# jacare.net
KiCad netlist of a schematic drawn in EAGLE
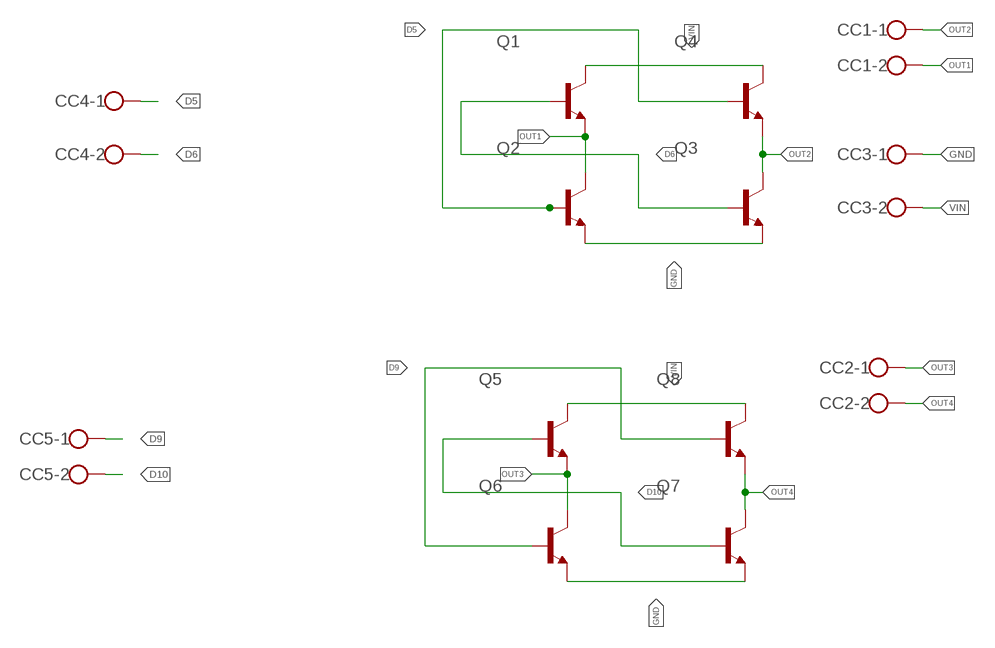
[diagram p0: schematic, sheet 1]

(export (version "E")
  (design (tool "Eeschema 10.0.6"))
  (components
    (comp (ref "CC1")
      (value "W237-102")
      (footprint "eagle-import:W237-102")
      (fields (field (name "MPN") "237-102"))
      (libsource (lib "eagle-import") (part "W237-102"))
    )
    (comp (ref "CC2")
      (value "W237-102")
      (footprint "eagle-import:W237-102")
      (fields (field (name "MPN") "237-102"))
      (libsource (lib "eagle-import") (part "W237-102"))
    )
    (comp (ref "CC3")
      (value "W237-102")
      (footprint "eagle-import:W237-102")
      (fields (field (name "MPN") "237-102"))
      (libsource (lib "eagle-import") (part "W237-102"))
    )
    (comp (ref "CC4")
      (value "W237-102")
      (footprint "eagle-import:W237-102")
      (fields (field (name "MPN") "237-102"))
      (libsource (lib "eagle-import") (part "W237-102"))
    )
    (comp (ref "CC5")
      (value "W237-102")
      (footprint "eagle-import:W237-102")
      (fields (field (name "MPN") "237-102"))
      (libsource (lib "eagle-import") (part "W237-102"))
    )
    (comp (ref "Q1")
      (value "-NPN-TO220V")
      (footprint "eagle-import:TO220V")
      (libsource (lib "eagle-import") (part "-NPN-TO220V"))
    )
    (comp (ref "Q2")
      (value "-NPN-TO220V")
      (footprint "eagle-import:TO220V")
      (libsource (lib "eagle-import") (part "-NPN-TO220V"))
    )
    (comp (ref "Q3")
      (value "-NPN-TO220V")
      (footprint "eagle-import:TO220V")
      (libsource (lib "eagle-import") (part "-NPN-TO220V"))
    )
    (comp (ref "Q4")
      (value "-NPN-TO220V")
      (footprint "eagle-import:TO220V")
      (libsource (lib "eagle-import") (part "-NPN-TO220V"))
    )
    (comp (ref "Q5")
      (value "-NPN-TO220V")
      (footprint "eagle-import:TO220V")
      (libsource (lib "eagle-import") (part "-NPN-TO220V"))
    )
    (comp (ref "Q6")
      (value "-NPN-TO220V")
      (footprint "eagle-import:TO220V")
      (libsource (lib "eagle-import") (part "-NPN-TO220V"))
    )
    (comp (ref "Q7")
      (value "-NPN-TO220V")
      (footprint "eagle-import:TO220V")
      (libsource (lib "eagle-import") (part "-NPN-TO220V"))
    )
    (comp (ref "Q8")
      (value "-NPN-TO220V")
      (footprint "eagle-import:TO220V")
      (libsource (lib "eagle-import") (part "-NPN-TO220V"))
    )
  )
  (nets
    (net (code "1") (name "D5") (class "Default")
      (node (ref "CC4") (pin "1") (pinfunction "KL_1") (pintype "passive"))
      (node (ref "Q2") (pin "1") (pinfunction "B_1") (pintype "passive"))
      (node (ref "Q4") (pin "1") (pinfunction "B_1") (pintype "passive"))
    )
    (net (code "2") (name "D6") (class "Default")
      (node (ref "CC4") (pin "2") (pinfunction "KL_2") (pintype "passive"))
      (node (ref "Q1") (pin "1") (pinfunction "B_1") (pintype "passive"))
      (node (ref "Q3") (pin "1") (pinfunction "B_1") (pintype "passive"))
    )
    (net (code "3") (name "D9") (class "Default")
      (node (ref "CC5") (pin "1") (pinfunction "KL_1") (pintype "passive"))
      (node (ref "Q6") (pin "1") (pinfunction "B_1") (pintype "passive"))
      (node (ref "Q8") (pin "1") (pinfunction "B_1") (pintype "passive"))
    )
    (net (code "4") (name "D10") (class "Default")
      (node (ref "CC5") (pin "2") (pinfunction "KL_2") (pintype "passive"))
      (node (ref "Q5") (pin "1") (pinfunction "B_1") (pintype "passive"))
      (node (ref "Q7") (pin "1") (pinfunction "B_1") (pintype "passive"))
    )
    (net (code "5") (name "GND") (class "Default")
      (node (ref "CC3") (pin "1") (pinfunction "KL_1") (pintype "passive"))
      (node (ref "Q2") (pin "3") (pinfunction "E_3") (pintype "passive"))
      (node (ref "Q3") (pin "3") (pinfunction "E_3") (pintype "passive"))
      (node (ref "Q6") (pin "3") (pinfunction "E_3") (pintype "passive"))
      (node (ref "Q7") (pin "3") (pinfunction "E_3") (pintype "passive"))
    )
    (net (code "6") (name "OUT1") (class "Default")
      (node (ref "CC1") (pin "2") (pinfunction "KL_2") (pintype "passive"))
      (node (ref "Q1") (pin "3") (pinfunction "E_3") (pintype "passive"))
      (node (ref "Q2") (pin "2") (pinfunction "C_2") (pintype "passive"))
    )
    (net (code "7") (name "OUT2") (class "Default")
      (node (ref "CC1") (pin "1") (pinfunction "KL_1") (pintype "passive"))
      (node (ref "Q3") (pin "2") (pinfunction "C_2") (pintype "passive"))
      (node (ref "Q4") (pin "3") (pinfunction "E_3") (pintype "passive"))
    )
    (net (code "8") (name "OUT3") (class "Default")
      (node (ref "CC2") (pin "1") (pinfunction "KL_1") (pintype "passive"))
      (node (ref "Q5") (pin "3") (pinfunction "E_3") (pintype "passive"))
      (node (ref "Q6") (pin "2") (pinfunction "C_2") (pintype "passive"))
    )
    (net (code "9") (name "OUT4") (class "Default")
      (node (ref "CC2") (pin "2") (pinfunction "KL_2") (pintype "passive"))
      (node (ref "Q7") (pin "2") (pinfunction "C_2") (pintype "passive"))
      (node (ref "Q8") (pin "3") (pinfunction "E_3") (pintype "passive"))
    )
    (net (code "10") (name "VIN") (class "Default")
      (node (ref "CC3") (pin "2") (pinfunction "KL_2") (pintype "passive"))
      (node (ref "Q1") (pin "2") (pinfunction "C_2") (pintype "passive"))
      (node (ref "Q4") (pin "2") (pinfunction "C_2") (pintype "passive"))
      (node (ref "Q5") (pin "2") (pinfunction "C_2") (pintype "passive"))
      (node (ref "Q8") (pin "2") (pinfunction "C_2") (pintype "passive"))
    )
  )
)
